# EXP430G2_node.net
KiCad netlist of a schematic drawn in EAGLE
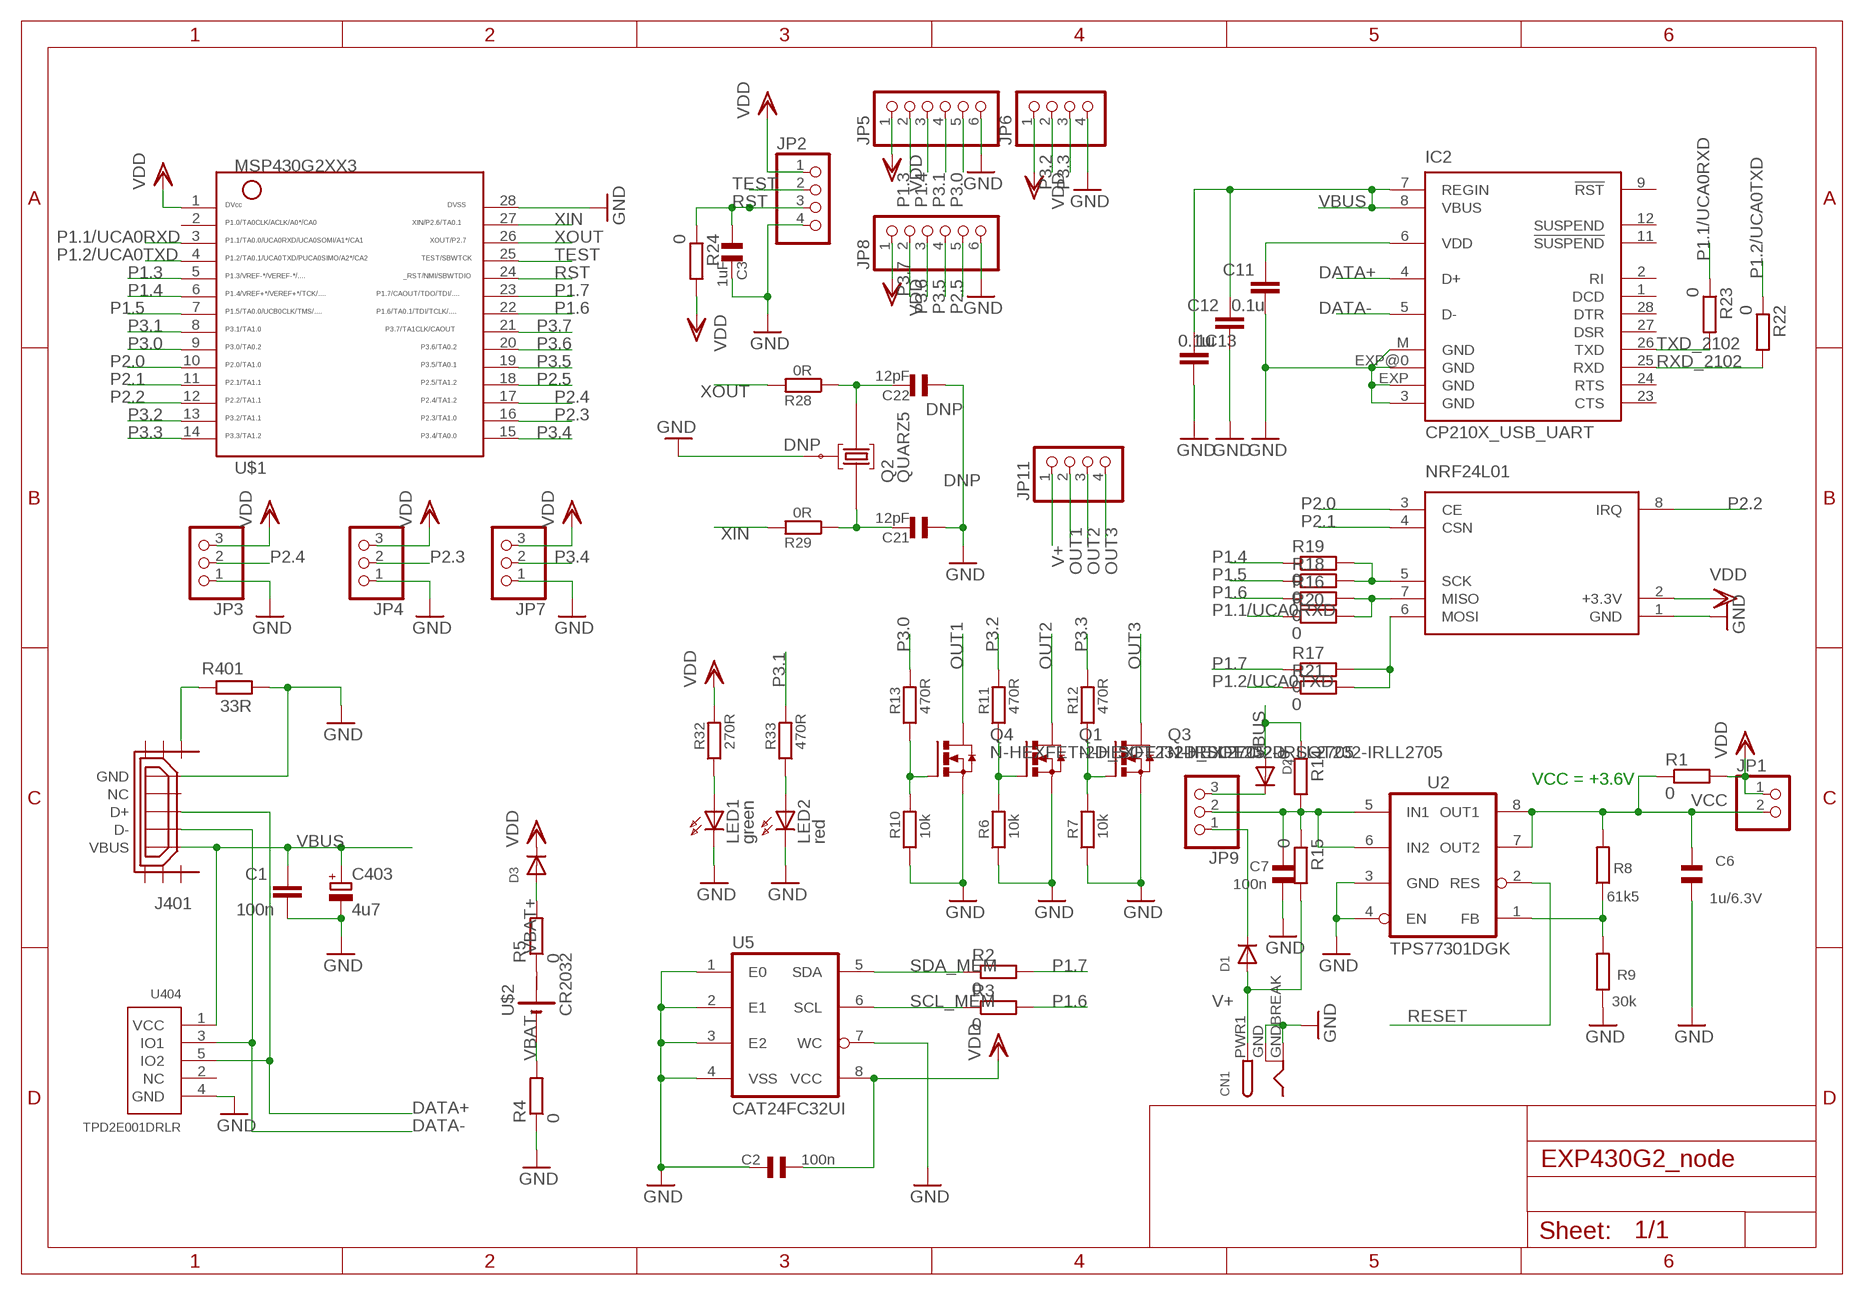
[diagram p0: schematic, sheet 1]

(export (version "E")
  (design (tool "Eeschema 10.0.6"))
  (components
    (comp (ref "C1")
      (value "100n")
      (footprint "eagle-import:C0603")
      (libsource (lib "eagle-import") (part "C-EUC0603"))
    )
    (comp (ref "C2")
      (value "100n")
      (footprint "eagle-import:0603")
      (libsource (lib "eagle-import") (part "C_SMD0603"))
    )
    (comp (ref "C3")
      (value "1uF")
      (footprint "eagle-import:0603")
      (libsource (lib "eagle-import") (part "ssmd_C_SMD0603"))
    )
    (comp (ref "C6")
      (value "1u/6.3V")
      (footprint "eagle-import:0603")
      (libsource (lib "eagle-import") (part "C_SMD0603"))
    )
    (comp (ref "C7")
      (value "100n")
      (footprint "eagle-import:0603")
      (libsource (lib "eagle-import") (part "C_SMD0603"))
    )
    (comp (ref "C11")
      (value "0.1u")
      (footprint "eagle-import:C0603")
      (libsource (lib "eagle-import") (part "C-EUC0603"))
    )
    (comp (ref "C12")
      (value "1u")
      (footprint "eagle-import:C0603")
      (libsource (lib "eagle-import") (part "C-EUC0603"))
    )
    (comp (ref "C13")
      (value "0.1u")
      (footprint "eagle-import:C0603")
      (libsource (lib "eagle-import") (part "C-EUC0603"))
    )
    (comp (ref "C21")
      (value "12pF")
      (footprint "eagle-import:0603")
      (libsource (lib "eagle-import") (part "ssmd_C_SMD0603"))
    )
    (comp (ref "C22")
      (value "12pF")
      (footprint "eagle-import:0603")
      (libsource (lib "eagle-import") (part "ssmd_C_SMD0603"))
    )
    (comp (ref "C403")
      (value "4u7")
      (footprint "eagle-import:A_3216-18R")
      (libsource (lib "eagle-import") (part "CPOL-EUA/3216-18R"))
    )
    (comp (ref "CN1")
      (value "DCBARRELSMT")
      (footprint "eagle-import:DCJACK_2MM_SMT")
      (libsource (lib "eagle-import") (part "DCBARRELSMT"))
    )
    (comp (ref "D1")
      (value "DIODESOT23_REFLOW")
      (footprint "eagle-import:SOT23-R")
      (libsource (lib "eagle-import") (part "DIODESOT23_REFLOW"))
    )
    (comp (ref "D2")
      (value "DIODESOT23_REFLOW")
      (footprint "eagle-import:SOT23-R")
      (libsource (lib "eagle-import") (part "DIODESOT23_REFLOW"))
    )
    (comp (ref "D3")
      (value "DIODESOT23_REFLOW")
      (footprint "eagle-import:SOT23-R")
      (libsource (lib "eagle-import") (part "DIODESOT23_REFLOW"))
    )
    (comp (ref "IC2")
      (value "CP210X_USB_UART")
      (footprint "eagle-import:MLP28")
      (libsource (lib "eagle-import") (part "CP210X_USB_UART"))
    )
    (comp (ref "J401")
      (value "USB_MICRO_FLIPPED")
      (footprint "eagle-import:HIROSE-ZX62R-B-5P")
      (libsource (lib "eagle-import") (part "USB_MICRO_FLIPPED"))
    )
    (comp (ref "JP1")
      (value "PINHD-1X2")
      (footprint "eagle-import:1X02")
      (libsource (lib "eagle-import") (part "PINHD-1X2"))
    )
    (comp (ref "JP2")
      (value "PINHD-1X4")
      (footprint "eagle-import:1X04")
      (libsource (lib "eagle-import") (part "PINHD-1X4"))
    )
    (comp (ref "JP3")
      (value "PINHD-1X3")
      (footprint "eagle-import:1X03")
      (libsource (lib "eagle-import") (part "pinhead_PINHD-1X3"))
    )
    (comp (ref "JP4")
      (value "PINHD-1X3_2.00")
      (footprint "eagle-import:1X03M")
      (libsource (lib "eagle-import") (part "PINHD-1X3_2.00"))
    )
    (comp (ref "JP5")
      (value "PINHD-1X6_2.00")
      (footprint "eagle-import:1X06M")
      (libsource (lib "eagle-import") (part "PINHD-1X6_2.00"))
    )
    (comp (ref "JP6")
      (value "PINHD-1X4_2.00")
      (footprint "eagle-import:1X04M")
      (libsource (lib "eagle-import") (part "PINHD-1X4_2.00"))
    )
    (comp (ref "JP7")
      (value "PINHD-1X3")
      (footprint "eagle-import:1X03")
      (libsource (lib "eagle-import") (part "PINHD-1X3"))
    )
    (comp (ref "JP8")
      (value "PINHD-1X6_2.00")
      (footprint "eagle-import:1X06M")
      (libsource (lib "eagle-import") (part "PINHD-1X6_2.00"))
    )
    (comp (ref "JP9")
      (value "PINHD-1X3")
      (footprint "eagle-import:1X03")
      (libsource (lib "eagle-import") (part "PINHD-1X3"))
    )
    (comp (ref "JP11")
      (value "PINHD-1X4_2.00")
      (footprint "eagle-import:1X04M")
      (libsource (lib "eagle-import") (part "PINHD-1X4_2.00"))
    )
    (comp (ref "LED1")
      (value "green")
      (footprint "eagle-import:DIODE0603")
      (libsource (lib "eagle-import") (part "LED_0603D0603"))
    )
    (comp (ref "LED2")
      (value "red")
      (footprint "eagle-import:DIODE0603")
      (libsource (lib "eagle-import") (part "LED_0603D0603"))
    )
    (comp (ref "NRF24L01")
      (value "NRF24L01HP")
      (footprint "eagle-import:NRF24L01_HP")
      (libsource (lib "eagle-import") (part "NRF24L01HP"))
    )
    (comp (ref "Q1")
      (value "N-HEXFET-2D_SOT232-IRLL2705")
      (footprint "eagle-import:SOT223")
      (libsource (lib "eagle-import") (part "N-HEXFET-2D_?-SOT232IRLL2705"))
    )
    (comp (ref "Q2")
      (value "QUARZ5")
      (footprint "eagle-import:QUARZ5")
      (libsource (lib "eagle-import") (part "QUARZ5"))
    )
    (comp (ref "Q3")
      (value "N-HEXFET-2D_SOT232-IRLL2705")
      (footprint "eagle-import:SOT223")
      (libsource (lib "eagle-import") (part "N-HEXFET-2D_?-SOT232IRLL2705"))
    )
    (comp (ref "Q4")
      (value "N-HEXFET-2D_SOT232-IRLL2705")
      (footprint "eagle-import:SOT223")
      (libsource (lib "eagle-import") (part "N-HEXFET-2D_?-SOT232IRLL2705"))
    )
    (comp (ref "R1")
      (value "0")
      (footprint "eagle-import:R0201")
      (libsource (lib "eagle-import") (part "resistor_R-EU_R0201"))
    )
    (comp (ref "R2")
      (value "0")
      (footprint "eagle-import:R0201")
      (libsource (lib "eagle-import") (part "resistor_R-EU_R0201"))
    )
    (comp (ref "R3")
      (value "0")
      (footprint "eagle-import:R0201")
      (libsource (lib "eagle-import") (part "resistor_R-EU_R0201"))
    )
    (comp (ref "R4")
      (value "0")
      (footprint "eagle-import:R0201")
      (libsource (lib "eagle-import") (part "resistor_R-EU_R0201"))
    )
    (comp (ref "R5")
      (value "0")
      (footprint "eagle-import:R0201")
      (libsource (lib "eagle-import") (part "resistor_R-EU_R0201"))
    )
    (comp (ref "R6")
      (value "10k")
      (footprint "eagle-import:0603")
      (libsource (lib "eagle-import") (part "ssmd_R_SMDR0603"))
    )
    (comp (ref "R7")
      (value "10k")
      (footprint "eagle-import:0603")
      (libsource (lib "eagle-import") (part "ssmd_R_SMDR0603"))
    )
    (comp (ref "R8")
      (value "61k5")
      (footprint "eagle-import:0603")
      (libsource (lib "eagle-import") (part "R_SMDR0603"))
    )
    (comp (ref "R9")
      (value "30k")
      (footprint "eagle-import:0603")
      (libsource (lib "eagle-import") (part "R_SMDR0603"))
    )
    (comp (ref "R10")
      (value "10k")
      (footprint "eagle-import:0603")
      (libsource (lib "eagle-import") (part "ssmd_R_SMDR0603"))
    )
    (comp (ref "R11")
      (value "470R")
      (footprint "eagle-import:0603")
      (libsource (lib "eagle-import") (part "ssmd_R_SMDR0603"))
    )
    (comp (ref "R12")
      (value "470R")
      (footprint "eagle-import:0603")
      (libsource (lib "eagle-import") (part "ssmd_R_SMDR0603"))
    )
    (comp (ref "R13")
      (value "470R")
      (footprint "eagle-import:0603")
      (libsource (lib "eagle-import") (part "ssmd_R_SMDR0603"))
    )
    (comp (ref "R14")
      (value "0")
      (footprint "eagle-import:R0201")
      (libsource (lib "eagle-import") (part "resistor_R-EU_R0201"))
    )
    (comp (ref "R15")
      (value "0")
      (footprint "eagle-import:R0201")
      (libsource (lib "eagle-import") (part "resistor_R-EU_R0201"))
    )
    (comp (ref "R16")
      (value "0")
      (footprint "eagle-import:R0201")
      (libsource (lib "eagle-import") (part "resistor_R-EU_R0201"))
    )
    (comp (ref "R17")
      (value "0")
      (footprint "eagle-import:R0201")
      (libsource (lib "eagle-import") (part "resistor_R-EU_R0201"))
    )
    (comp (ref "R18")
      (value "0")
      (footprint "eagle-import:R0201")
      (libsource (lib "eagle-import") (part "resistor_R-EU_R0201"))
    )
    (comp (ref "R19")
      (value "0")
      (footprint "eagle-import:R0201")
      (libsource (lib "eagle-import") (part "resistor_R-EU_R0201"))
    )
    (comp (ref "R20")
      (value "0")
      (footprint "eagle-import:R0201")
      (libsource (lib "eagle-import") (part "resistor_R-EU_R0201"))
    )
    (comp (ref "R21")
      (value "0")
      (footprint "eagle-import:R0201")
      (libsource (lib "eagle-import") (part "resistor_R-EU_R0201"))
    )
    (comp (ref "R22")
      (value "0")
      (footprint "eagle-import:R0201")
      (libsource (lib "eagle-import") (part "resistor_R-EU_R0201"))
    )
    (comp (ref "R23")
      (value "0")
      (footprint "eagle-import:R0201")
      (libsource (lib "eagle-import") (part "resistor_R-EU_R0201"))
    )
    (comp (ref "R24")
      (value "0")
      (footprint "eagle-import:R0201")
      (libsource (lib "eagle-import") (part "resistor_R-EU_R0201"))
    )
    (comp (ref "R28")
      (value "0R")
      (footprint "eagle-import:0603")
      (libsource (lib "eagle-import") (part "ssmd_R_SMDR0603"))
    )
    (comp (ref "R29")
      (value "0R")
      (footprint "eagle-import:0603")
      (libsource (lib "eagle-import") (part "ssmd_R_SMDR0603"))
    )
    (comp (ref "R32")
      (value "270R")
      (footprint "eagle-import:0603")
      (libsource (lib "eagle-import") (part "ssmd_R_SMDR0603"))
    )
    (comp (ref "R33")
      (value "470R")
      (footprint "eagle-import:0603")
      (libsource (lib "eagle-import") (part "ssmd_R_SMDR0603"))
    )
    (comp (ref "R401")
      (value "33R")
      (footprint "eagle-import:R0603")
      (libsource (lib "eagle-import") (part "R-EU_R0603"))
    )
    (comp (ref "U$1")
      (value "G2XX3---PW28")
      (footprint "eagle-import:PW28")
      (libsource (lib "eagle-import") (part "G2XX3---PW28"))
    )
    (comp (ref "U$2")
      (value "CR2032")
      (footprint "eagle-import:CR2032")
      (libsource (lib "eagle-import") (part "CR2032"))
    )
    (comp (ref "U2")
      (value "TPS77301DGK")
      (footprint "eagle-import:MSOP8")
      (libsource (lib "eagle-import") (part "TPS773XX"))
    )
    (comp (ref "U5")
      (value "CAT24FC32UI")
      (footprint "eagle-import:TSSOP8")
      (libsource (lib "eagle-import") (part "M24XXX"))
    )
    (comp (ref "U404")
      (value "TPD2E001DRLR")
      (footprint "eagle-import:TPD2E001-DRL")
      (libsource (lib "eagle-import") (part "TPD2E001"))
    )
  )
  (nets
    (net (code "1") (name "/DATA+") (class "Default")
      (node (ref "IC2") (pin "4") (pinfunction "D+_4") (pintype "bidirectional"))
      (node (ref "J401") (pin "D+") (pinfunction "D+_D+") (pintype "input"))
      (node (ref "U404") (pin "5") (pinfunction "IO2_5") (pintype "bidirectional"))
    )
    (net (code "2") (name "/DATA-") (class "Default")
      (node (ref "IC2") (pin "5") (pinfunction "D-_5") (pintype "bidirectional"))
      (node (ref "J401") (pin "D-") (pinfunction "D-_D-") (pintype "input"))
      (node (ref "U404") (pin "3") (pinfunction "IO1_3") (pintype "bidirectional"))
    )
    (net (code "3") (name "/OUT1") (class "Default")
      (node (ref "JP11") (pin "2") (pinfunction "2_2") (pintype "passive"))
      (node (ref "Q4") (pin "2") (pinfunction "D_2") (pintype "passive"))
      (node (ref "Q4") (pin "4") (pinfunction "D_4") (pintype "passive"))
    )
    (net (code "4") (name "/OUT2") (class "Default")
      (node (ref "JP11") (pin "3") (pinfunction "3_3") (pintype "passive"))
      (node (ref "Q1") (pin "2") (pinfunction "D_2") (pintype "passive"))
      (node (ref "Q1") (pin "4") (pinfunction "D_4") (pintype "passive"))
    )
    (net (code "5") (name "/OUT3") (class "Default")
      (node (ref "JP11") (pin "4") (pinfunction "4_4") (pintype "passive"))
      (node (ref "Q3") (pin "2") (pinfunction "D_2") (pintype "passive"))
      (node (ref "Q3") (pin "4") (pinfunction "D_4") (pintype "passive"))
    )
    (net (code "6") (name "/P1.1{slash}UCA0RXD") (class "Default")
      (node (ref "R20") (pin "1") (pinfunction "1_1") (pintype "passive"))
      (node (ref "R23") (pin "1") (pinfunction "1_1") (pintype "passive"))
      (node (ref "U$1") (pin "3") (pinfunction "3_3") (pintype "bidirectional"))
    )
    (net (code "7") (name "/P1.2{slash}UCA0TXD") (class "Default")
      (node (ref "R21") (pin "1") (pinfunction "1_1") (pintype "passive"))
      (node (ref "R22") (pin "1") (pinfunction "1_1") (pintype "passive"))
      (node (ref "U$1") (pin "4") (pinfunction "4_4") (pintype "bidirectional"))
    )
    (net (code "8") (name "/P1.3") (class "Default")
      (node (ref "JP5") (pin "2") (pinfunction "2_2") (pintype "passive"))
      (node (ref "U$1") (pin "5") (pinfunction "5_5") (pintype "bidirectional"))
    )
    (net (code "9") (name "/P1.4") (class "Default")
      (node (ref "JP5") (pin "3") (pinfunction "3_3") (pintype "passive"))
      (node (ref "R19") (pin "1") (pinfunction "1_1") (pintype "passive"))
      (node (ref "U$1") (pin "6") (pinfunction "6_6") (pintype "bidirectional"))
    )
    (net (code "10") (name "/P1.5") (class "Default")
      (node (ref "R18") (pin "1") (pinfunction "1_1") (pintype "passive"))
      (node (ref "U$1") (pin "7") (pinfunction "7_7") (pintype "bidirectional"))
    )
    (net (code "11") (name "/P1.6") (class "Default")
      (node (ref "R16") (pin "1") (pinfunction "1_1") (pintype "passive"))
      (node (ref "R3") (pin "2") (pinfunction "2_2") (pintype "passive"))
      (node (ref "U$1") (pin "22") (pinfunction "22_22") (pintype "bidirectional"))
    )
    (net (code "12") (name "/P1.7") (class "Default")
      (node (ref "R17") (pin "1") (pinfunction "1_1") (pintype "passive"))
      (node (ref "R2") (pin "2") (pinfunction "2_2") (pintype "passive"))
      (node (ref "U$1") (pin "23") (pinfunction "23_23") (pintype "bidirectional"))
    )
    (net (code "13") (name "/P2.0") (class "Default")
      (node (ref "NRF24L01") (pin "3") (pinfunction "CE_3") (pintype "bidirectional"))
      (node (ref "U$1") (pin "10") (pinfunction "10_10") (pintype "bidirectional"))
    )
    (net (code "14") (name "/P2.1") (class "Default")
      (node (ref "NRF24L01") (pin "4") (pinfunction "CSN_4") (pintype "bidirectional"))
      (node (ref "U$1") (pin "11") (pinfunction "11_11") (pintype "bidirectional"))
    )
    (net (code "15") (name "/P2.2") (class "Default")
      (node (ref "NRF24L01") (pin "8") (pinfunction "IRQ_8") (pintype "bidirectional"))
      (node (ref "U$1") (pin "12") (pinfunction "12_12") (pintype "bidirectional"))
    )
    (net (code "16") (name "/P2.3") (class "Default")
      (node (ref "JP4") (pin "2") (pinfunction "2_2") (pintype "passive"))
      (node (ref "U$1") (pin "16") (pinfunction "16_16") (pintype "bidirectional"))
    )
    (net (code "17") (name "/P2.4") (class "Default")
      (node (ref "JP3") (pin "2") (pinfunction "2_2") (pintype "passive"))
      (node (ref "U$1") (pin "17") (pinfunction "17_17") (pintype "bidirectional"))
    )
    (net (code "18") (name "/P2.5") (class "Default")
      (node (ref "JP8") (pin "5") (pinfunction "5_5") (pintype "passive"))
      (node (ref "U$1") (pin "18") (pinfunction "18_18") (pintype "bidirectional"))
    )
    (net (code "19") (name "/P3.0") (class "Default")
      (node (ref "JP5") (pin "5") (pinfunction "5_5") (pintype "passive"))
      (node (ref "R13") (pin "2") (pinfunction "2_2") (pintype "passive"))
      (node (ref "U$1") (pin "9") (pinfunction "9_9") (pintype "bidirectional"))
    )
    (net (code "20") (name "/P3.1") (class "Default")
      (node (ref "JP5") (pin "4") (pinfunction "4_4") (pintype "passive"))
      (node (ref "R33") (pin "2") (pinfunction "2_2") (pintype "passive"))
      (node (ref "U$1") (pin "8") (pinfunction "8_8") (pintype "bidirectional"))
    )
    (net (code "21") (name "/P3.2") (class "Default")
      (node (ref "JP6") (pin "2") (pinfunction "2_2") (pintype "passive"))
      (node (ref "R11") (pin "2") (pinfunction "2_2") (pintype "passive"))
      (node (ref "U$1") (pin "13") (pinfunction "13_13") (pintype "bidirectional"))
    )
    (net (code "22") (name "/P3.3") (class "Default")
      (node (ref "JP6") (pin "3") (pinfunction "3_3") (pintype "passive"))
      (node (ref "R12") (pin "2") (pinfunction "2_2") (pintype "passive"))
      (node (ref "U$1") (pin "14") (pinfunction "14_14") (pintype "bidirectional"))
    )
    (net (code "23") (name "/P3.4") (class "Default")
      (node (ref "JP7") (pin "2") (pinfunction "2_2") (pintype "passive"))
      (node (ref "U$1") (pin "15") (pinfunction "15_15") (pintype "bidirectional"))
    )
    (net (code "24") (name "/P3.5") (class "Default")
      (node (ref "JP8") (pin "4") (pinfunction "4_4") (pintype "passive"))
      (node (ref "U$1") (pin "19") (pinfunction "19_19") (pintype "bidirectional"))
    )
    (net (code "25") (name "/P3.6") (class "Default")
      (node (ref "JP8") (pin "3") (pinfunction "3_3") (pintype "passive"))
      (node (ref "U$1") (pin "20") (pinfunction "20_20") (pintype "bidirectional"))
    )
    (net (code "26") (name "/P3.7") (class "Default")
      (node (ref "JP8") (pin "2") (pinfunction "2_2") (pintype "passive"))
      (node (ref "U$1") (pin "21") (pinfunction "21_21") (pintype "bidirectional"))
    )
    (net (code "27") (name "/RESET") (class "Default")
      (node (ref "U2") (pin "2") (pinfunction "RES_2") (pintype "output"))
    )
    (net (code "28") (name "/RST") (class "Default")
      (node (ref "C3") (pin "1") (pinfunction "1_1") (pintype "passive"))
      (node (ref "JP2") (pin "3") (pinfunction "3_3") (pintype "passive"))
      (node (ref "R24") (pin "1") (pinfunction "1_1") (pintype "passive"))
      (node (ref "U$1") (pin "24") (pinfunction "24_24") (pintype "bidirectional"))
    )
    (net (code "29") (name "/RXD_2102") (class "Default")
      (node (ref "IC2") (pin "25") (pinfunction "RXD_25") (pintype "input"))
      (node (ref "R22") (pin "2") (pinfunction "2_2") (pintype "passive"))
    )
    (net (code "30") (name "/SCL_MEM") (class "Default")
      (node (ref "R3") (pin "1") (pinfunction "1_1") (pintype "passive"))
      (node (ref "U5") (pin "6") (pinfunction "SCL_6") (pintype "power_in"))
    )
    (net (code "31") (name "/SDA_MEM") (class "Default")
      (node (ref "R2") (pin "1") (pinfunction "1_1") (pintype "passive"))
      (node (ref "U5") (pin "5") (pinfunction "SDA_5") (pintype "power_in"))
    )
    (net (code "32") (name "/TEST") (class "Default")
      (node (ref "JP2") (pin "2") (pinfunction "2_2") (pintype "passive"))
      (node (ref "U$1") (pin "25") (pinfunction "25_25") (pintype "bidirectional"))
    )
    (net (code "33") (name "/TXD_2102") (class "Default")
      (node (ref "IC2") (pin "26") (pinfunction "TXD_26") (pintype "output"))
      (node (ref "R23") (pin "2") (pinfunction "2_2") (pintype "passive"))
    )
    (net (code "34") (name "/V+") (class "Default")
      (node (ref "CN1") (pin "PWR1") (pinfunction "PWR_PWR1") (pintype "power_in"))
      (node (ref "D1") (pin "1") (pinfunction "A_1") (pintype "passive"))
      (node (ref "JP11") (pin "1") (pinfunction "1_1") (pintype "passive"))
      (node (ref "R15") (pin "2") (pinfunction "2_2") (pintype "passive"))
    )
    (net (code "36") (name "/VBAT+") (class "Default")
      (node (ref "R5") (pin "1") (pinfunction "1_1") (pintype "passive"))
      (node (ref "U$2") (pin "P$1") (pinfunction "+_P$1") (pintype "passive"))
    )
    (net (code "37") (name "/VBAT-") (class "Default")
      (node (ref "R4") (pin "2") (pinfunction "2_2") (pintype "passive"))
      (node (ref "U$2") (pin "P$2") (pinfunction "-_P$2") (pintype "passive"))
    )
    (net (code "38") (name "/VBUS") (class "Default")
      (node (ref "C1") (pin "1") (pinfunction "1_1") (pintype "passive"))
      (node (ref "C12") (pin "1") (pinfunction "1_1") (pintype "passive"))
      (node (ref "C13") (pin "1") (pinfunction "1_1") (pintype "passive"))
      (node (ref "C403") (pin "+") (pinfunction "+_+") (pintype "passive"))
      (node (ref "D2") (pin "1") (pinfunction "A_1") (pintype "passive"))
      (node (ref "IC2") (pin "7") (pinfunction "REGIN_7") (pintype "passive"))
      (node (ref "IC2") (pin "8") (pinfunction "VBUS_8") (pintype "input"))
      (node (ref "J401") (pin "VBUS") (pinfunction "VBUS_VBUS") (pintype "input"))
      (node (ref "R14") (pin "1") (pinfunction "1_1") (pintype "passive"))
      (node (ref "U404") (pin "1") (pinfunction "VCC_1") (pintype "power_in"))
    )
    (net (code "39") (name "/VCC") (class "Default")
      (node (ref "C6") (pin "1") (pinfunction "1_1") (pintype "passive"))
      (node (ref "JP1") (pin "2") (pinfunction "2_2") (pintype "passive"))
      (node (ref "R1") (pin "1") (pinfunction "1_1") (pintype "passive"))
      (node (ref "R8") (pin "2") (pinfunction "2_2") (pintype "passive"))
      (node (ref "U2") (pin "7") (pinfunction "OUT2_7") (pintype "power_in"))
      (node (ref "U2") (pin "8") (pinfunction "OUT1_8") (pintype "power_in"))
    )
    (net (code "40") (name "/XIN") (class "Default")
      (node (ref "R29") (pin "2") (pinfunction "2_2") (pintype "passive"))
      (node (ref "U$1") (pin "27") (pinfunction "27_27") (pintype "bidirectional"))
    )
    (net (code "41") (name "/XOUT") (class "Default")
      (node (ref "R28") (pin "2") (pinfunction "2_2") (pintype "passive"))
      (node (ref "U$1") (pin "26") (pinfunction "26_26") (pintype "bidirectional"))
    )
    (net (code "42") (name "GND") (class "Default")
      (node (ref "C1") (pin "2") (pinfunction "2_2") (pintype "passive"))
      (node (ref "C11") (pin "2") (pinfunction "2_2") (pintype "passive"))
      (node (ref "C12") (pin "2") (pinfunction "2_2") (pintype "passive"))
      (node (ref "C13") (pin "2") (pinfunction "2_2") (pintype "passive"))
      (node (ref "C2") (pin "2") (pinfunction "2_2") (pintype "passive"))
      (node (ref "C21") (pin "1") (pinfunction "1_1") (pintype "passive"))
      (node (ref "C22") (pin "1") (pinfunction "1_1") (pintype "passive"))
      (node (ref "C3") (pin "2") (pinfunction "2_2") (pintype "passive"))
      (node (ref "C403") (pin "-") (pinfunction "-_-") (pintype "passive"))
      (node (ref "C6") (pin "2") (pinfunction "2_2") (pintype "passive"))
      (node (ref "C7") (pin "1") (pinfunction "1_1") (pintype "passive"))
      (node (ref "CN1") (pin "GND") (pinfunction "GNDBREAK_GND") (pintype "power_in"))
      (node (ref "CN1") (pin "GNDBREAK") (pinfunction "GND_GNDBREAK") (pintype "power_in"))
      (node (ref "IC2") (pin "3") (pinfunction "GND_3") (pintype "power_in"))
      (node (ref "IC2") (pin "EXP") (pinfunction "GND_EXP") (pintype "power_in"))
      (node (ref "IC2") (pin "EXP@0") (pinfunction "GND_EXP@0") (pintype "power_in"))
      (node (ref "IC2") (pin "M") (pinfunction "GND_M") (pintype "power_in"))
      (node (ref "J401") (pin "GND") (pinfunction "GND_GND") (pintype "input"))
      (node (ref "JP2") (pin "4") (pinfunction "4_4") (pintype "passive"))
      (node (ref "JP3") (pin "1") (pinfunction "1_1") (pintype "passive"))
      (node (ref "JP4") (pin "1") (pinfunction "1_1") (pintype "passive"))
      (node (ref "JP5") (pin "6") (pinfunction "6_6") (pintype "passive"))
      (node (ref "JP6") (pin "4") (pinfunction "4_4") (pintype "passive"))
      (node (ref "JP7") (pin "1") (pinfunction "1_1") (pintype "passive"))
      (node (ref "JP8") (pin "6") (pinfunction "6_6") (pintype "passive"))
      (node (ref "LED1") (pin "K") (pinfunction "C_K") (pintype "passive"))
      (node (ref "LED2") (pin "K") (pinfunction "C_K") (pintype "passive"))
      (node (ref "NRF24L01") (pin "1") (pinfunction "GND_1") (pintype "power_in"))
      (node (ref "Q1") (pin "3") (pinfunction "S_3") (pintype "passive"))
      (node (ref "Q2") (pin "GND@0") (pinfunction "0_GND@0") (pintype "passive"))
      (node (ref "Q3") (pin "3") (pinfunction "S_3") (pintype "passive"))
      (node (ref "Q4") (pin "3") (pinfunction "S_3") (pintype "passive"))
      (node (ref "R10") (pin "1") (pinfunction "1_1") (pintype "passive"))
      (node (ref "R4") (pin "1") (pinfunction "1_1") (pintype "passive"))
      (node (ref "R401") (pin "2") (pinfunction "2_2") (pintype "passive"))
      (node (ref "R6") (pin "1") (pinfunction "1_1") (pintype "passive"))
      (node (ref "R7") (pin "1") (pinfunction "1_1") (pintype "passive"))
      (node (ref "R9") (pin "1") (pinfunction "1_1") (pintype "passive"))
      (node (ref "U$1") (pin "28") (pinfunction "28_28") (pintype "bidirectional"))
      (node (ref "U2") (pin "3") (pinfunction "GND_3") (pintype "power_in"))
      (node (ref "U2") (pin "4") (pinfunction "EN_4") (pintype "input"))
      (node (ref "U404") (pin "4") (pinfunction "GND_4") (pintype "power_in"))
      (node (ref "U5") (pin "1") (pinfunction "E0_1") (pintype "input"))
      (node (ref "U5") (pin "2") (pinfunction "E1_2") (pintype "input"))
      (node (ref "U5") (pin "3") (pinfunction "E2_3") (pintype "power_in"))
      (node (ref "U5") (pin "4") (pinfunction "VSS_4") (pintype "input"))
      (node (ref "U5") (pin "7") (pinfunction "WC_7") (pintype "output"))
    )
    (net (code "43") (name "Net-(C21-Pad2)") (class "Default")
      (node (ref "C21") (pin "2") (pinfunction "2_2") (pintype "passive"))
      (node (ref "Q2") (pin "2") (pinfunction "2_2") (pintype "passive"))
      (node (ref "R29") (pin "1") (pinfunction "1_1") (pintype "passive"))
    )
    (net (code "44") (name "Net-(C22-Pad2)") (class "Default")
      (node (ref "C22") (pin "2") (pinfunction "2_2") (pintype "passive"))
      (node (ref "Q2") (pin "1") (pinfunction "1_1") (pintype "passive"))
      (node (ref "R28") (pin "1") (pinfunction "1_1") (pintype "passive"))
    )
    (net (code "45") (name "Net-(D1-C)") (class "Default")
      (node (ref "D1") (pin "3") (pinfunction "C_3") (pintype "passive"))
      (node (ref "JP9") (pin "1") (pinfunction "1_1") (pintype "passive"))
    )
    (net (code "46") (name "Net-(D2-C)") (class "Default")
      (node (ref "D2") (pin "3") (pinfunction "C_3") (pintype "passive"))
      (node (ref "JP9") (pin "3") (pinfunction "3_3") (pintype "passive"))
    )
    (net (code "47") (name "Net-(D3-A)") (class "Default")
      (node (ref "D3") (pin "1") (pinfunction "A_1") (pintype "passive"))
      (node (ref "R5") (pin "2") (pinfunction "2_2") (pintype "passive"))
    )
    (net (code "48") (name "Net-(IC2-VDD)") (class "Default")
      (node (ref "C11") (pin "1") (pinfunction "1_1") (pintype "passive"))
      (node (ref "IC2") (pin "6") (pinfunction "VDD_6") (pintype "power_in"))
    )
    (net (code "49") (name "Net-(J401-PadSHIELD1)") (class "Default")
      (node (ref "J401") (pin "SHIELD1") (pinfunction "SHIELD1_SHIELD1") (pintype "bidirectional"))
      (node (ref "R401") (pin "1") (pinfunction "1_1") (pintype "passive"))
    )
    (net (code "50") (name "Net-(LED1-PadA)") (class "Default")
      (node (ref "LED1") (pin "A") (pinfunction "A_A") (pintype "passive"))
      (node (ref "R32") (pin "1") (pinfunction "1_1") (pintype "passive"))
    )
    (net (code "51") (name "Net-(LED2-PadA)") (class "Default")
      (node (ref "LED2") (pin "A") (pinfunction "A_A") (pintype "passive"))
      (node (ref "R33") (pin "1") (pinfunction "1_1") (pintype "passive"))
    )
    (net (code "52") (name "Net-(NRF24L01-MISO)") (class "Default")
      (node (ref "NRF24L01") (pin "7") (pinfunction "MISO_7") (pintype "bidirectional"))
      (node (ref "R16") (pin "2") (pinfunction "2_2") (pintype "passive"))
      (node (ref "R20") (pin "2") (pinfunction "2_2") (pintype "passive"))
    )
    (net (code "53") (name "Net-(NRF24L01-MOSI)") (class "Default")
      (node (ref "NRF24L01") (pin "6") (pinfunction "MOSI_6") (pintype "bidirectional"))
      (node (ref "R17") (pin "2") (pinfunction "2_2") (pintype "passive"))
      (node (ref "R21") (pin "2") (pinfunction "2_2") (pintype "passive"))
    )
    (net (code "54") (name "Net-(NRF24L01-SCK)") (class "Default")
      (node (ref "NRF24L01") (pin "5") (pinfunction "SCK_5") (pintype "bidirectional"))
      (node (ref "R18") (pin "2") (pinfunction "2_2") (pintype "passive"))
      (node (ref "R19") (pin "2") (pinfunction "2_2") (pintype "passive"))
    )
    (net (code "55") (name "Net-(Q1-G)") (class "Default")
      (node (ref "Q1") (pin "1") (pinfunction "G_1") (pintype "passive"))
      (node (ref "R11") (pin "1") (pinfunction "1_1") (pintype "passive"))
      (node (ref "R6") (pin "2") (pinfunction "2_2") (pintype "passive"))
    )
    (net (code "56") (name "Net-(Q3-G)") (class "Default")
      (node (ref "Q3") (pin "1") (pinfunction "G_1") (pintype "passive"))
      (node (ref "R12") (pin "1") (pinfunction "1_1") (pintype "passive"))
      (node (ref "R7") (pin "2") (pinfunction "2_2") (pintype "passive"))
    )
    (net (code "57") (name "Net-(Q4-G)") (class "Default")
      (node (ref "Q4") (pin "1") (pinfunction "G_1") (pintype "passive"))
      (node (ref "R10") (pin "2") (pinfunction "2_2") (pintype "passive"))
      (node (ref "R13") (pin "1") (pinfunction "1_1") (pintype "passive"))
    )
    (net (code "58") (name "Net-(U2-FB)") (class "Default")
      (node (ref "R8") (pin "1") (pinfunction "1_1") (pintype "passive"))
      (node (ref "R9") (pin "2") (pinfunction "2_2") (pintype "passive"))
      (node (ref "U2") (pin "1") (pinfunction "FB_1") (pintype "input"))
    )
    (net (code "59") (name "Net-(U2-IN1)") (class "Default")
      (node (ref "C7") (pin "2") (pinfunction "2_2") (pintype "passive"))
      (node (ref "JP9") (pin "2") (pinfunction "2_2") (pintype "passive"))
      (node (ref "R14") (pin "2") (pinfunction "2_2") (pintype "passive"))
      (node (ref "R15") (pin "1") (pinfunction "1_1") (pintype "passive"))
      (node (ref "U2") (pin "5") (pinfunction "IN1_5") (pintype "input"))
      (node (ref "U2") (pin "6") (pinfunction "IN2_6") (pintype "input"))
    )
    (net (code "60") (name "VDD") (class "Default")
      (node (ref "C2") (pin "1") (pinfunction "1_1") (pintype "passive"))
      (node (ref "D3") (pin "3") (pinfunction "C_3") (pintype "passive"))
      (node (ref "JP1") (pin "1") (pinfunction "1_1") (pintype "passive"))
      (node (ref "JP2") (pin "1") (pinfunction "1_1") (pintype "passive"))
      (node (ref "JP3") (pin "3") (pinfunction "3_3") (pintype "passive"))
      (node (ref "JP4") (pin "3") (pinfunction "3_3") (pintype "passive"))
      (node (ref "JP5") (pin "1") (pinfunction "1_1") (pintype "passive"))
      (node (ref "JP6") (pin "1") (pinfunction "1_1") (pintype "passive"))
      (node (ref "JP7") (pin "3") (pinfunction "3_3") (pintype "passive"))
      (node (ref "JP8") (pin "1") (pinfunction "1_1") (pintype "passive"))
      (node (ref "NRF24L01") (pin "2") (pinfunction "+3.3V_2") (pintype "power_in"))
      (node (ref "R1") (pin "2") (pinfunction "2_2") (pintype "passive"))
      (node (ref "R24") (pin "2") (pinfunction "2_2") (pintype "passive"))
      (node (ref "R32") (pin "2") (pinfunction "2_2") (pintype "passive"))
      (node (ref "U$1") (pin "1") (pinfunction "1_1") (pintype "bidirectional"))
      (node (ref "U5") (pin "8") (pinfunction "VCC_8") (pintype "input"))
    )
    (net (code "61") (name "unconnected-(IC2-CTS-Pad23)") (class "Default")
      (node (ref "IC2") (pin "23") (pinfunction "CTS_23") (pintype "input"))
    )
    (net (code "62") (name "unconnected-(IC2-DCD-Pad1)") (class "Default")
      (node (ref "IC2") (pin "1") (pinfunction "DCD_1") (pintype "input"))
    )
    (net (code "63") (name "unconnected-(IC2-DSR-Pad27)") (class "Default")
      (node (ref "IC2") (pin "27") (pinfunction "DSR_27") (pintype "input"))
    )
    (net (code "64") (name "unconnected-(IC2-DTR-Pad28)") (class "Default")
      (node (ref "IC2") (pin "28") (pinfunction "DTR_28") (pintype "output"))
    )
    (net (code "65") (name "unconnected-(IC2-RI-Pad2)") (class "Default")
      (node (ref "IC2") (pin "2") (pinfunction "RI_2") (pintype "input"))
    )
    (net (code "66") (name "unconnected-(IC2-RTS-Pad24)") (class "Default")
      (node (ref "IC2") (pin "24") (pinfunction "RTS_24") (pintype "output"))
    )
    (net (code "67") (name "unconnected-(IC2-SUSPEND-Pad12)") (class "Default")
      (node (ref "IC2") (pin "12") (pinfunction "SUSPEND_12") (pintype "output"))
    )
    (net (code "68") (name "unconnected-(IC2-~{RST}-Pad9)") (class "Default")
      (node (ref "IC2") (pin "9") (pinfunction "~{RST}_9") (pintype "bidirectional"))
    )
    (net (code "69") (name "unconnected-(IC2-~{SUSPEND}-Pad11)") (class "Default")
      (node (ref "IC2") (pin "11") (pinfunction "~{SUSPEND}_11") (pintype "output"))
    )
    (net (code "70") (name "unconnected-(J401-PadNC)") (class "Default")
      (node (ref "J401") (pin "NC") (pinfunction "NC_NC") (pintype "input"))
    )
    (net (code "71") (name "unconnected-(J401-PadSHIELD2)") (class "Default")
      (node (ref "J401") (pin "SHIELD2") (pinfunction "SHIELD2_SHIELD2") (pintype "bidirectional"))
    )
    (net (code "72") (name "unconnected-(J401-PadSHIELD3)") (class "Default")
      (node (ref "J401") (pin "SHIELD3") (pinfunction "SHIELD3_SHIELD3") (pintype "bidirectional"))
    )
    (net (code "73") (name "unconnected-(J401-PadSHIELD4)") (class "Default")
      (node (ref "J401") (pin "SHIELD4") (pinfunction "SHIELD4_SHIELD4") (pintype "bidirectional"))
    )
    (net (code "74") (name "unconnected-(J401-PadSHIELD5)") (class "Default")
      (node (ref "J401") (pin "SHIELD5") (pinfunction "SHIELD5_SHIELD5") (pintype "bidirectional"))
    )
    (net (code "75") (name "unconnected-(J401-PadSHIELD6)") (class "Default")
      (node (ref "J401") (pin "SHIELD6") (pinfunction "SHIELD6_SHIELD6") (pintype "bidirectional"))
    )
    (net (code "76") (name "unconnected-(U$1-Pad2)") (class "Default")
      (node (ref "U$1") (pin "2") (pinfunction "2_2") (pintype "bidirectional"))
    )
    (net (code "77") (name "unconnected-(U404-NC-Pad2)") (class "Default")
      (node (ref "U404") (pin "2") (pinfunction "NC_2") (pintype "no_connect"))
    )
  )
)
